# Deckelplatine_v091.net
KiCad netlist of a schematic drawn in EAGLE
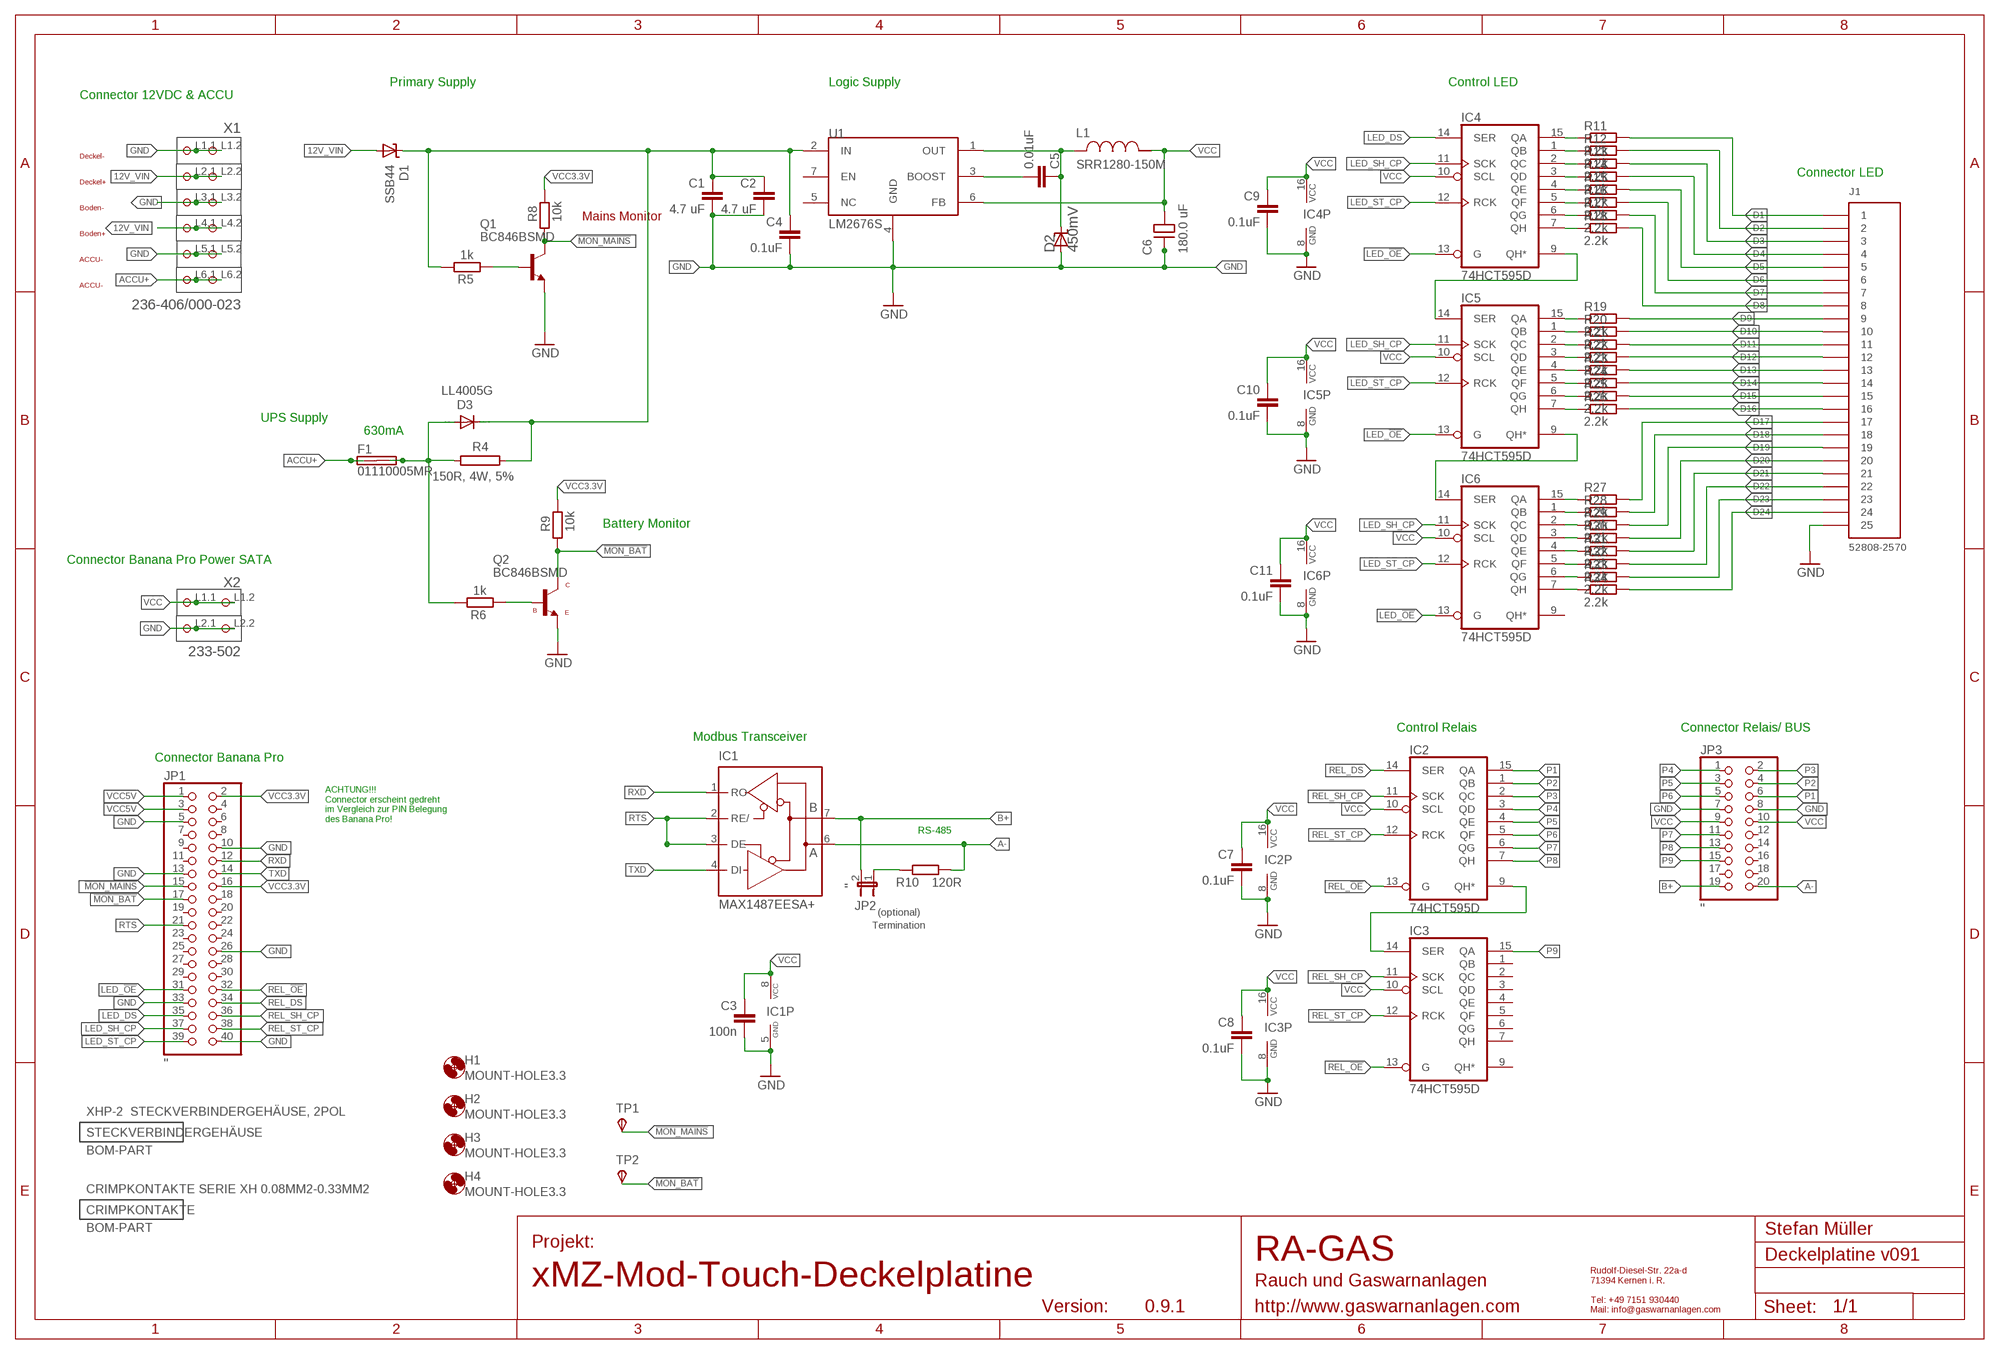
[diagram p0: schematic, sheet 1]

(export (version "E")
  (design (tool "Eeschema 10.0.6"))
  (components
    (comp (ref "C1")
      (value "4.7 uF")
      (footprint "eagle-import:GRM21BR61E475MA12L")
      (fields (field (name "MANUFACTURER_PART_NUMBER") "GRM21BR61E475MA12L") (field (name "MF") "MURATA"))
      (libsource (lib "eagle-import") (part "GRM21BR61E475MA12L"))
    )
    (comp (ref "C2")
      (value "4.7 uF")
      (footprint "eagle-import:GRM21BR61E475MA12L")
      (fields (field (name "MANUFACTURER_PART_NUMBER") "GRM21BR61E475MA12L") (field (name "MF") "MURATA"))
      (libsource (lib "eagle-import") (part "GRM21BR61E475MA12L"))
    )
    (comp (ref "C3")
      (value "100n")
      (footprint "eagle-import:C0603")
      (fields
        (field (name "MF") "KEMET")
        (field (name "MPN") "C0603C104K8RACTU")
        (field (name "PARTNO") "ECHU-16-100N")
      )
      (libsource (lib "eagle-import") (part "C-EUC0603"))
    )
    (comp (ref "C4")
      (value "0.1uF")
      (footprint "eagle-import:0805")
      (fields (field (name "MANUFACTURER_PART_NUMBER") "08053C104KAT2A") (field (name "MF") "AVX"))
      (libsource (lib "eagle-import") (part "08053C104KAT2A"))
    )
    (comp (ref "C5")
      (value "0.01uF")
      (footprint "eagle-import:GRM216R71H103KA01D")
      (fields (field (name "MANUFACTURER_PART_NUMBER") "GRM216R71H103KA01D") (field (name "MF") "MURATA"))
      (libsource (lib "eagle-import") (part "GRM216R71H103KA01D"))
    )
    (comp (ref "C6")
      (value "180.0 uF")
      (footprint "eagle-import:SM_RADIAL_10MM")
      (fields
        (field (name "MF") "PANASONIC ELECTRONIC COMPONENTS")
        (field (name "MPN") "16SVP180MX")
        (field (name "PARTNO") "RAD FC 560/35")
      )
      (libsource (lib "eagle-import") (part "16SVP180MSM_RADIAL_10MM"))
    )
    (comp (ref "C7")
      (value "0.1uF")
      (footprint "eagle-import:C0603")
      (fields
        (field (name "MF") "KEMET")
        (field (name "MPN") "C0603C104K8RACTU")
        (field (name "PARTNO") "SMD TAN.0,1/35")
      )
      (libsource (lib "eagle-import") (part "C-EUC0603"))
    )
    (comp (ref "C8")
      (value "0.1uF")
      (footprint "eagle-import:C0603")
      (fields
        (field (name "MF") "KEMET")
        (field (name "MPN") "C0603C104K8RACTU")
        (field (name "PARTNO") "SMD TAN.0,1/35")
      )
      (libsource (lib "eagle-import") (part "C-EUC0603"))
    )
    (comp (ref "C9")
      (value "0.1uF")
      (footprint "eagle-import:C0603")
      (fields
        (field (name "MF") "KEMET")
        (field (name "MPN") "C0603C104K8RACTU")
        (field (name "PARTNO") "SMD TAN.0,1/35")
      )
      (libsource (lib "eagle-import") (part "C-EUC0603"))
    )
    (comp (ref "C10")
      (value "0.1uF")
      (footprint "eagle-import:C0603")
      (fields
        (field (name "MF") "KEMET")
        (field (name "MPN") "C0603C104K8RACTU")
        (field (name "PARTNO") "SMD TAN.0,1/35")
      )
      (libsource (lib "eagle-import") (part "C-EUC0603"))
    )
    (comp (ref "C11")
      (value "0.1uF")
      (footprint "eagle-import:C0603")
      (fields
        (field (name "MF") "KEMET")
        (field (name "MPN") "C0603C104K8RACTU")
        (field (name "PARTNO") "SMD TAN.0,1/35")
      )
      (libsource (lib "eagle-import") (part "C-EUC0603"))
    )
    (comp (ref "D1")
      (value "SSB44")
      (footprint "eagle-import:SMBJ")
      (fields (field (name "MF") "VISHAY") (field (name "MPN") "SSB44-E3/52T"))
      (libsource (lib "eagle-import") (part "SUPPRESSOR-SMBJ"))
    )
    (comp (ref "D2")
      (value "450mV")
      (footprint "eagle-import:SMB")
      (fields (field (name "MANUFACTURER_PART_NUMBER") "B340LB-13-F") (field (name "MF") "DIODES INC."))
      (libsource (lib "eagle-import") (part "B340LB-13-F"))
    )
    (comp (ref "D3")
      (value "LL4005G")
      (footprint "eagle-import:MELF-MLL41")
      (fields (field (name "MF") "TAIWAN SEMICONDUCTOR"))
      (libsource (lib "eagle-import") (part "DIODE-MELF-MLL41"))
    )
    (comp (ref "F1")
      (value "01110005MR")
      (footprint "eagle-import:01110005MR")
      (fields (field (name "MF") "LITTELFUSE"))
      (libsource (lib "eagle-import") (part "01110005MR"))
    )
    (comp (ref "H1")
      (value "MOUNT-HOLE3.3")
      (footprint "eagle-import:3,3")
      (libsource (lib "eagle-import") (part "MOUNT-HOLE3.3"))
    )
    (comp (ref "H2")
      (value "MOUNT-HOLE3.3")
      (footprint "eagle-import:3,3")
      (libsource (lib "eagle-import") (part "MOUNT-HOLE3.3"))
    )
    (comp (ref "H3")
      (value "MOUNT-HOLE3.3")
      (footprint "eagle-import:3,3")
      (libsource (lib "eagle-import") (part "MOUNT-HOLE3.3"))
    )
    (comp (ref "H4")
      (value "MOUNT-HOLE3.3")
      (footprint "eagle-import:3,3")
      (libsource (lib "eagle-import") (part "MOUNT-HOLE3.3"))
    )
    (comp (ref "IC1")
      (value "MAX1487EESA+")
      (footprint "eagle-import:SO08")
      (fields
        (field (name "MF") "MAXIM")
        (field (name "MPN") "MAX481CSA")
        (field (name "MF_1") "MAXIM INTEGRATED PRODUCTS")
        (field (name "MPN_1") "MAX1487EESA+")
        (field (name "OC_FARNELL") "1593310")
        (field (name "PARTNO") "MAX481CSA")
      )
      (libsource (lib "eagle-import") (part "MAX481CSA"))
    )
    (comp (ref "IC2")
      (value "74HCT595D")
      (footprint "eagle-import:SO16")
      (fields
        (field (name "MF") "NXP")
        (field (name "MPN") "74HCT595D")
        (field (name "OC_FARNELL") "2098004")
        (field (name "PARTNO") "SMD HC 595")
      )
      (libsource (lib "eagle-import") (part "74595DHCT"))
    )
    (comp (ref "IC3")
      (value "74HCT595D")
      (footprint "eagle-import:SO16")
      (fields
        (field (name "MF") "NXP")
        (field (name "MPN") "74HCT595D")
        (field (name "OC_FARNELL") "2098004")
        (field (name "PARTNO") "SMD HC 595")
      )
      (libsource (lib "eagle-import") (part "74595DHCT"))
    )
    (comp (ref "IC4")
      (value "74HCT595D")
      (footprint "eagle-import:SO16")
      (fields
        (field (name "MF") "NXP")
        (field (name "MPN") "74HCT595D")
        (field (name "OC_FARNELL") "2098004")
        (field (name "PARTNO") "SMD HC 595")
      )
      (libsource (lib "eagle-import") (part "74595DHCT"))
    )
    (comp (ref "IC5")
      (value "74HCT595D")
      (footprint "eagle-import:SO16")
      (fields
        (field (name "MF") "NXP")
        (field (name "MPN") "74HCT595D")
        (field (name "OC_FARNELL") "2098004")
        (field (name "PARTNO") "SMD HC 595")
      )
      (libsource (lib "eagle-import") (part "74595DHCT"))
    )
    (comp (ref "IC6")
      (value "74HCT595D")
      (footprint "eagle-import:SO16")
      (fields
        (field (name "MF") "NXP")
        (field (name "MPN") "74HCT595D")
        (field (name "OC_FARNELL") "2098004")
        (field (name "PARTNO") "SMD HC 595")
      )
      (libsource (lib "eagle-import") (part "74595DHCT"))
    )
    (comp (ref "J1")
      (value "52808-2570")
      (footprint "eagle-import:52808-2570")
      (fields (field (name "MF") "MOLEX"))
      (libsource (lib "eagle-import") (part "52808-2570"))
    )
    (comp (ref "JP1")
      (value "''")
      (footprint "eagle-import:2X20")
      (fields (field (name "MF") "HARWIN") (field (name "MPN") "M20-6112045"))
      (libsource (lib "eagle-import") (part "PINHD-2X20"))
    )
    (comp (ref "JP2")
      (value "''")
      (footprint "eagle-import:JP1")
      (fields (field (name "MF") "TE CONNECTIVITY / AMP") (field (name "MPN") "825433-2"))
      (libsource (lib "eagle-import") (part "JP1E"))
    )
    (comp (ref "JP3")
      (value "''")
      (footprint "eagle-import:2X10")
      (fields (field (name "MF") "TE CONNECTIVITY / AMP") (field (name "MPN") "5103308-5"))
      (libsource (lib "eagle-import") (part "PINHD-2X10"))
    )
    (comp (ref "L1")
      (value "SRR1280-150M")
      (footprint "eagle-import:SRR1280")
      (fields (field (name "MF") "COILCRAFT") (field (name "MPN") "MSS1278-153MLD"))
      (libsource (lib "eagle-import") (part "SRR1280-150M"))
    )
    (comp (ref "Q1")
      (value "BC846BSMD")
      (footprint "eagle-import:SOT23")
      (fields (field (name "MF") "NXP") (field (name "MPN") "BC846,215"))
      (libsource (lib "eagle-import") (part "BC846SMDB"))
    )
    (comp (ref "Q2")
      (value "BC846BSMD")
      (footprint "eagle-import:SOT23")
      (fields (field (name "MF") "NXP") (field (name "MPN") "BC846,215"))
      (libsource (lib "eagle-import") (part "BC846SMDB"))
    )
    (comp (ref "R4")
      (value "150R, 4W, 5%")
      (footprint "eagle-import:KH206-8")
      (fields
        (field (name "MF") "TE CONNECTIVITY / CGS")
        (field (name "MPN") "ER74150RJT")
        (field (name "OC_FARNELL") "1751842")
      )
      (libsource (lib "eagle-import") (part "RKH206-8"))
    )
    (comp (ref "R5")
      (value "1k")
      (footprint "eagle-import:R1210")
      (fields (field (name "MF") "PANASONIC ELECTRONIC COMPONENTS") (field (name "MPN") "ERJP14F1001U"))
      (libsource (lib "eagle-import") (part "rcl_R-EU_R1210"))
    )
    (comp (ref "R6")
      (value "1k")
      (footprint "eagle-import:R1210")
      (fields (field (name "MF") "PANASONIC ELECTRONIC COMPONENTS") (field (name "MPN") "ERJP14F1001U"))
      (libsource (lib "eagle-import") (part "rcl_R-EU_R1210"))
    )
    (comp (ref "R8")
      (value "10k")
      (footprint "eagle-import:R1210")
      (fields (field (name "MF") "PANASONIC ELECTRONIC COMPONENTS") (field (name "MPN") "ERJP14F1002U"))
      (libsource (lib "eagle-import") (part "rcl_R-EU_R1210"))
    )
    (comp (ref "R9")
      (value "10k")
      (footprint "eagle-import:R1210")
      (fields (field (name "MF") "PANASONIC ELECTRONIC COMPONENTS") (field (name "MPN") "ERJP14F1002U"))
      (libsource (lib "eagle-import") (part "rcl_R-EU_R1210"))
    )
    (comp (ref "R10")
      (value "120R")
      (footprint "eagle-import:R1206")
      (fields (field (name "MF") "TE CONNECTIVITY") (field (name "MPN") "CRGH1206F120R"))
      (libsource (lib "eagle-import") (part "rcl_R-EU_R1206"))
    )
    (comp (ref "R11")
      (value "2.2k")
      (footprint "eagle-import:R0603")
      (fields
        (field (name "MF") "YAGEO (PHYCOMP)")
        (field (name "MPN") "RC0603FR-072K2L")
        (field (name "PARTNO") "SMD-0603 2,2K")
      )
      (libsource (lib "eagle-import") (part "R-EU_R0603"))
    )
    (comp (ref "R12")
      (value "2.2k")
      (footprint "eagle-import:R0603")
      (fields
        (field (name "MF") "YAGEO (PHYCOMP)")
        (field (name "MPN") "RC0603FR-072K2L")
        (field (name "PARTNO") "SMD-0603 2,2K")
      )
      (libsource (lib "eagle-import") (part "R-EU_R0603"))
    )
    (comp (ref "R13")
      (value "2.2k")
      (footprint "eagle-import:R0603")
      (fields
        (field (name "MF") "YAGEO (PHYCOMP)")
        (field (name "MPN") "RC0603FR-072K2L")
        (field (name "PARTNO") "SMD-0603 2,2K")
      )
      (libsource (lib "eagle-import") (part "R-EU_R0603"))
    )
    (comp (ref "R14")
      (value "2.2k")
      (footprint "eagle-import:R0603")
      (fields
        (field (name "MF") "YAGEO (PHYCOMP)")
        (field (name "MPN") "RC0603FR-072K2L")
        (field (name "PARTNO") "SMD-0603 2,2K")
      )
      (libsource (lib "eagle-import") (part "R-EU_R0603"))
    )
    (comp (ref "R15")
      (value "2.2k")
      (footprint "eagle-import:R0603")
      (fields
        (field (name "MF") "YAGEO (PHYCOMP)")
        (field (name "MPN") "RC0603FR-072K2L")
        (field (name "PARTNO") "SMD-0603 2,2K")
      )
      (libsource (lib "eagle-import") (part "R-EU_R0603"))
    )
    (comp (ref "R16")
      (value "2.2k")
      (footprint "eagle-import:R0603")
      (fields
        (field (name "MF") "YAGEO (PHYCOMP)")
        (field (name "MPN") "RC0603FR-072K2L")
        (field (name "PARTNO") "SMD-0603 2,2K")
      )
      (libsource (lib "eagle-import") (part "R-EU_R0603"))
    )
    (comp (ref "R17")
      (value "2.2k")
      (footprint "eagle-import:R0603")
      (fields
        (field (name "MF") "YAGEO (PHYCOMP)")
        (field (name "MPN") "RC0603FR-072K2L")
        (field (name "PARTNO") "SMD-0603 2,2K")
      )
      (libsource (lib "eagle-import") (part "R-EU_R0603"))
    )
    (comp (ref "R18")
      (value "2.2k")
      (footprint "eagle-import:R0603")
      (fields
        (field (name "MF") "YAGEO (PHYCOMP)")
        (field (name "MPN") "RC0603FR-072K2L")
        (field (name "PARTNO") "SMD-0603 2,2K")
      )
      (libsource (lib "eagle-import") (part "R-EU_R0603"))
    )
    (comp (ref "R19")
      (value "2.2k")
      (footprint "eagle-import:R0603")
      (fields
        (field (name "MF") "YAGEO (PHYCOMP)")
        (field (name "MPN") "RC0603FR-072K2L")
        (field (name "PARTNO") "SMD-0603 2,2K")
      )
      (libsource (lib "eagle-import") (part "R-EU_R0603"))
    )
    (comp (ref "R20")
      (value "2.2k")
      (footprint "eagle-import:R0603")
      (fields
        (field (name "MF") "YAGEO (PHYCOMP)")
        (field (name "MPN") "RC0603FR-072K2L")
        (field (name "PARTNO") "SMD-0603 2,2K")
      )
      (libsource (lib "eagle-import") (part "R-EU_R0603"))
    )
    (comp (ref "R21")
      (value "2.2k")
      (footprint "eagle-import:R0603")
      (fields
        (field (name "MF") "YAGEO (PHYCOMP)")
        (field (name "MPN") "RC0603FR-072K2L")
        (field (name "PARTNO") "SMD-0603 2,2K")
      )
      (libsource (lib "eagle-import") (part "R-EU_R0603"))
    )
    (comp (ref "R22")
      (value "2.2k")
      (footprint "eagle-import:R0603")
      (fields
        (field (name "MF") "YAGEO (PHYCOMP)")
        (field (name "MPN") "RC0603FR-072K2L")
        (field (name "PARTNO") "SMD-0603 2,2K")
      )
      (libsource (lib "eagle-import") (part "R-EU_R0603"))
    )
    (comp (ref "R23")
      (value "2.2k")
      (footprint "eagle-import:R0603")
      (fields
        (field (name "MF") "YAGEO (PHYCOMP)")
        (field (name "MPN") "RC0603FR-072K2L")
        (field (name "PARTNO") "SMD-0603 2,2K")
      )
      (libsource (lib "eagle-import") (part "R-EU_R0603"))
    )
    (comp (ref "R24")
      (value "2.2k")
      (footprint "eagle-import:R0603")
      (fields
        (field (name "MF") "YAGEO (PHYCOMP)")
        (field (name "MPN") "RC0603FR-072K2L")
        (field (name "PARTNO") "SMD-0603 2,2K")
      )
      (libsource (lib "eagle-import") (part "R-EU_R0603"))
    )
    (comp (ref "R25")
      (value "2.2k")
      (footprint "eagle-import:R0603")
      (fields
        (field (name "MF") "YAGEO (PHYCOMP)")
        (field (name "MPN") "RC0603FR-072K2L")
        (field (name "PARTNO") "SMD-0603 2,2K")
      )
      (libsource (lib "eagle-import") (part "R-EU_R0603"))
    )
    (comp (ref "R26")
      (value "2.2k")
      (footprint "eagle-import:R0603")
      (fields
        (field (name "MF") "YAGEO (PHYCOMP)")
        (field (name "MPN") "RC0603FR-072K2L")
        (field (name "PARTNO") "SMD-0603 2,2K")
      )
      (libsource (lib "eagle-import") (part "R-EU_R0603"))
    )
    (comp (ref "R27")
      (value "2.2k")
      (footprint "eagle-import:R0603")
      (fields
        (field (name "MF") "YAGEO (PHYCOMP)")
        (field (name "MPN") "RC0603FR-072K2L")
        (field (name "PARTNO") "SMD-0603 2,2K")
      )
      (libsource (lib "eagle-import") (part "R-EU_R0603"))
    )
    (comp (ref "R28")
      (value "2.2k")
      (footprint "eagle-import:R0603")
      (fields
        (field (name "MF") "YAGEO (PHYCOMP)")
        (field (name "MPN") "RC0603FR-072K2L")
        (field (name "PARTNO") "SMD-0603 2,2K")
      )
      (libsource (lib "eagle-import") (part "R-EU_R0603"))
    )
    (comp (ref "R29")
      (value "2.2k")
      (footprint "eagle-import:R0603")
      (fields
        (field (name "MF") "YAGEO (PHYCOMP)")
        (field (name "MPN") "RC0603FR-072K2L")
        (field (name "PARTNO") "SMD-0603 2,2K")
      )
      (libsource (lib "eagle-import") (part "R-EU_R0603"))
    )
    (comp (ref "R30")
      (value "2.2k")
      (footprint "eagle-import:R0603")
      (fields
        (field (name "MF") "YAGEO (PHYCOMP)")
        (field (name "MPN") "RC0603FR-072K2L")
        (field (name "PARTNO") "SMD-0603 2,2K")
      )
      (libsource (lib "eagle-import") (part "R-EU_R0603"))
    )
    (comp (ref "R31")
      (value "2.2k")
      (footprint "eagle-import:R0603")
      (fields
        (field (name "MF") "YAGEO (PHYCOMP)")
        (field (name "MPN") "RC0603FR-072K2L")
        (field (name "PARTNO") "SMD-0603 2,2K")
      )
      (libsource (lib "eagle-import") (part "R-EU_R0603"))
    )
    (comp (ref "R32")
      (value "2.2k")
      (footprint "eagle-import:R0603")
      (fields
        (field (name "MF") "YAGEO (PHYCOMP)")
        (field (name "MPN") "RC0603FR-072K2L")
        (field (name "PARTNO") "SMD-0603 2,2K")
      )
      (libsource (lib "eagle-import") (part "R-EU_R0603"))
    )
    (comp (ref "R33")
      (value "2.2k")
      (footprint "eagle-import:R0603")
      (fields
        (field (name "MF") "YAGEO (PHYCOMP)")
        (field (name "MPN") "RC0603FR-072K2L")
        (field (name "PARTNO") "SMD-0603 2,2K")
      )
      (libsource (lib "eagle-import") (part "R-EU_R0603"))
    )
    (comp (ref "R34")
      (value "2.2k")
      (footprint "eagle-import:R0603")
      (fields
        (field (name "MF") "YAGEO (PHYCOMP)")
        (field (name "MPN") "RC0603FR-072K2L")
        (field (name "PARTNO") "SMD-0603 2,2K")
      )
      (libsource (lib "eagle-import") (part "R-EU_R0603"))
    )
    (comp (ref "TP1")
      (value "TPSB1,27")
      (footprint "eagle-import:B1,27")
      (libsource (lib "eagle-import") (part "TPSB1,27"))
    )
    (comp (ref "TP2")
      (value "TPSB1,27")
      (footprint "eagle-import:B1,27")
      (libsource (lib "eagle-import") (part "TPSB1,27"))
    )
    (comp (ref "U1")
      (value "LM2676S")
      (footprint "eagle-import:TO-263-7")
      (fields (field (name "MF") "TEXAS INSTRUMENTS") (field (name "MPN") "LM2676S-5.0/NOPB"))
      (libsource (lib "eagle-import") (part "LM2676S"))
    )
    (comp (ref "X1")
      (value "236-406/000-023")
      (footprint "eagle-import:P-236-406")
      (fields (field (name "MF") "WAGO") (field (name "MPN") "236-406"))
      (libsource (lib "eagle-import") (part "236-406/000-023"))
    )
    (comp (ref "X2")
      (value "233-502")
      (footprint "eagle-import:P-233-502")
      (fields (field (name "MF") "WAGO") (field (name "MPN") "233-502."))
      (libsource (lib "eagle-import") (part "233-502"))
    )
  )
  (nets
    (net (code "1") (name "/LED_~{OE}") (class "Default")
      (node (ref "IC4") (pin "13") (pinfunction "G_13") (pintype "input"))
      (node (ref "IC5") (pin "13") (pinfunction "G_13") (pintype "input"))
      (node (ref "IC6") (pin "13") (pinfunction "G_13") (pintype "input"))
      (node (ref "JP1") (pin "31") (pinfunction "31_31") (pintype "passive"))
    )
    (net (code "2") (name "/REL_~{OE}") (class "Default")
      (node (ref "IC2") (pin "13") (pinfunction "G_13") (pintype "input"))
      (node (ref "IC3") (pin "13") (pinfunction "G_13") (pintype "input"))
      (node (ref "JP1") (pin "32") (pinfunction "32_32") (pintype "passive"))
    )
    (net (code "3") (name "/~{MON_BAT}") (class "Default")
      (node (ref "JP1") (pin "17") (pinfunction "17_17") (pintype "passive"))
      (node (ref "Q2") (pin "3") (pinfunction "C_3") (pintype "passive"))
      (node (ref "R9") (pin "1") (pinfunction "1_1") (pintype "passive"))
      (node (ref "TP2") (pin "TP") (pinfunction "PP_TP") (pintype "input"))
    )
    (net (code "4") (name "/~{MON_MAINS}") (class "Default")
      (node (ref "JP1") (pin "15") (pinfunction "15_15") (pintype "passive"))
      (node (ref "Q1") (pin "3") (pinfunction "C_3") (pintype "passive"))
      (node (ref "R8") (pin "1") (pinfunction "1_1") (pintype "passive"))
      (node (ref "TP1") (pin "TP") (pinfunction "PP_TP") (pintype "input"))
    )
    (net (code "5") (name "12V_VIN") (class "Default")
      (node (ref "C1") (pin "1") (pinfunction "1_1") (pintype "passive"))
      (node (ref "C2") (pin "1") (pinfunction "1_1") (pintype "passive"))
      (node (ref "C4") (pin "1") (pinfunction "1_1") (pintype "passive"))
      (node (ref "D1") (pin "A") (pinfunction "A_A") (pintype "passive"))
      (node (ref "D1") (pin "C") (pinfunction "C_C") (pintype "passive"))
      (node (ref "D3") (pin "C") (pinfunction "C_C") (pintype "passive"))
      (node (ref "R4") (pin "2") (pinfunction "2_2") (pintype "passive"))
      (node (ref "R5") (pin "2") (pinfunction "2_2") (pintype "passive"))
      (node (ref "U1") (pin "2") (pinfunction "IN_2") (pintype "power_in"))
      (node (ref "X1") (pin "L2.1") (pinfunction "P2.1_L2.1") (pintype "bidirectional"))
      (node (ref "X1") (pin "L2.2") (pinfunction "P2.2_L2.2") (pintype "bidirectional"))
      (node (ref "X1") (pin "L4.1") (pinfunction "P4.1_L4.1") (pintype "bidirectional"))
      (node (ref "X1") (pin "L4.2") (pinfunction "P4.2_L4.2") (pintype "bidirectional"))
    )
    (net (code "6") (name "A-") (class "Default")
      (node (ref "IC1") (pin "6") (pinfunction "A_6") (pintype "passive"))
      (node (ref "JP3") (pin "20") (pinfunction "20_20") (pintype "passive"))
      (node (ref "R10") (pin "2") (pinfunction "2_2") (pintype "passive"))
    )
    (net (code "7") (name "ACCU+") (class "Default")
      (node (ref "D3") (pin "A") (pinfunction "A_A") (pintype "passive"))
      (node (ref "F1") (pin "1A") (pinfunction "1A_1A") (pintype "passive"))
      (node (ref "F1") (pin "1B") (pinfunction "1B_1B") (pintype "passive"))
      (node (ref "F1") (pin "2A") (pinfunction "2A_2A") (pintype "passive"))
      (node (ref "F1") (pin "2B") (pinfunction "2B_2B") (pintype "passive"))
      (node (ref "R4") (pin "1") (pinfunction "1_1") (pintype "passive"))
      (node (ref "R6") (pin "2") (pinfunction "2_2") (pintype "passive"))
      (node (ref "X1") (pin "L6.1") (pinfunction "P6.1_L6.1") (pintype "bidirectional"))
      (node (ref "X1") (pin "L6.2") (pinfunction "P6.2_L6.2") (pintype "bidirectional"))
    )
    (net (code "8") (name "B+") (class "Default")
      (node (ref "IC1") (pin "7") (pinfunction "B_7") (pintype "passive"))
      (node (ref "JP2") (pin "2") (pinfunction "2_2") (pintype "passive"))
      (node (ref "JP3") (pin "19") (pinfunction "19_19") (pintype "passive"))
    )
    (net (code "9") (name "D1") (class "Default")
      (node (ref "J1") (pin "1") (pinfunction "1_1") (pintype "bidirectional"))
      (node (ref "R11") (pin "2") (pinfunction "2_2") (pintype "passive"))
    )
    (net (code "10") (name "D2") (class "Default")
      (node (ref "J1") (pin "2") (pinfunction "2_2") (pintype "bidirectional"))
      (node (ref "R12") (pin "2") (pinfunction "2_2") (pintype "passive"))
    )
    (net (code "11") (name "D3") (class "Default")
      (node (ref "J1") (pin "3") (pinfunction "3_3") (pintype "bidirectional"))
      (node (ref "R13") (pin "2") (pinfunction "2_2") (pintype "passive"))
    )
    (net (code "12") (name "D4") (class "Default")
      (node (ref "J1") (pin "4") (pinfunction "4_4") (pintype "bidirectional"))
      (node (ref "R14") (pin "2") (pinfunction "2_2") (pintype "passive"))
    )
    (net (code "13") (name "D5") (class "Default")
      (node (ref "J1") (pin "5") (pinfunction "5_5") (pintype "bidirectional"))
      (node (ref "R15") (pin "2") (pinfunction "2_2") (pintype "passive"))
    )
    (net (code "14") (name "D6") (class "Default")
      (node (ref "J1") (pin "6") (pinfunction "6_6") (pintype "bidirectional"))
      (node (ref "R16") (pin "2") (pinfunction "2_2") (pintype "passive"))
    )
    (net (code "15") (name "D7") (class "Default")
      (node (ref "J1") (pin "7") (pinfunction "7_7") (pintype "bidirectional"))
      (node (ref "R17") (pin "2") (pinfunction "2_2") (pintype "passive"))
    )
    (net (code "16") (name "D8") (class "Default")
      (node (ref "J1") (pin "8") (pinfunction "8_8") (pintype "bidirectional"))
      (node (ref "R18") (pin "2") (pinfunction "2_2") (pintype "passive"))
    )
    (net (code "17") (name "D9") (class "Default")
      (node (ref "J1") (pin "9") (pinfunction "9_9") (pintype "bidirectional"))
      (node (ref "R19") (pin "2") (pinfunction "2_2") (pintype "passive"))
    )
    (net (code "18") (name "D10") (class "Default")
      (node (ref "J1") (pin "10") (pinfunction "10_10") (pintype "bidirectional"))
      (node (ref "R20") (pin "2") (pinfunction "2_2") (pintype "passive"))
    )
    (net (code "19") (name "D11") (class "Default")
      (node (ref "J1") (pin "11") (pinfunction "11_11") (pintype "bidirectional"))
      (node (ref "R21") (pin "2") (pinfunction "2_2") (pintype "passive"))
    )
    (net (code "20") (name "D12") (class "Default")
      (node (ref "J1") (pin "12") (pinfunction "12_12") (pintype "bidirectional"))
      (node (ref "R22") (pin "2") (pinfunction "2_2") (pintype "passive"))
    )
    (net (code "21") (name "D13") (class "Default")
      (node (ref "J1") (pin "13") (pinfunction "13_13") (pintype "bidirectional"))
      (node (ref "R23") (pin "2") (pinfunction "2_2") (pintype "passive"))
    )
    (net (code "22") (name "D14") (class "Default")
      (node (ref "J1") (pin "14") (pinfunction "14_14") (pintype "bidirectional"))
      (node (ref "R24") (pin "2") (pinfunction "2_2") (pintype "passive"))
    )
    (net (code "23") (name "D15") (class "Default")
      (node (ref "J1") (pin "15") (pinfunction "15_15") (pintype "bidirectional"))
      (node (ref "R25") (pin "2") (pinfunction "2_2") (pintype "passive"))
    )
    (net (code "24") (name "D16") (class "Default")
      (node (ref "J1") (pin "16") (pinfunction "16_16") (pintype "bidirectional"))
      (node (ref "R26") (pin "2") (pinfunction "2_2") (pintype "passive"))
    )
    (net (code "25") (name "D17") (class "Default")
      (node (ref "J1") (pin "17") (pinfunction "17_17") (pintype "bidirectional"))
      (node (ref "R27") (pin "2") (pinfunction "2_2") (pintype "passive"))
    )
    (net (code "26") (name "D18") (class "Default")
      (node (ref "J1") (pin "18") (pinfunction "18_18") (pintype "bidirectional"))
      (node (ref "R28") (pin "2") (pinfunction "2_2") (pintype "passive"))
    )
    (net (code "27") (name "D19") (class "Default")
      (node (ref "J1") (pin "19") (pinfunction "19_19") (pintype "bidirectional"))
      (node (ref "R29") (pin "2") (pinfunction "2_2") (pintype "passive"))
    )
    (net (code "28") (name "D20") (class "Default")
      (node (ref "J1") (pin "20") (pinfunction "20_20") (pintype "bidirectional"))
      (node (ref "R30") (pin "2") (pinfunction "2_2") (pintype "passive"))
    )
    (net (code "29") (name "D21") (class "Default")
      (node (ref "J1") (pin "21") (pinfunction "21_21") (pintype "bidirectional"))
      (node (ref "R31") (pin "2") (pinfunction "2_2") (pintype "passive"))
    )
    (net (code "30") (name "D22") (class "Default")
      (node (ref "J1") (pin "22") (pinfunction "22_22") (pintype "bidirectional"))
      (node (ref "R32") (pin "2") (pinfunction "2_2") (pintype "passive"))
    )
    (net (code "31") (name "D23") (class "Default")
      (node (ref "J1") (pin "23") (pinfunction "23_23") (pintype "bidirectional"))
      (node (ref "R33") (pin "2") (pinfunction "2_2") (pintype "passive"))
    )
    (net (code "32") (name "D24") (class "Default")
      (node (ref "J1") (pin "24") (pinfunction "24_24") (pintype "bidirectional"))
      (node (ref "R34") (pin "2") (pinfunction "2_2") (pintype "passive"))
    )
    (net (code "33") (name "GND") (class "Default")
      (node (ref "C1") (pin "2") (pinfunction "2_2") (pintype "passive"))
      (node (ref "C10") (pin "2") (pinfunction "2_2") (pintype "passive"))
      (node (ref "C11") (pin "2") (pinfunction "2_2") (pintype "passive"))
      (node (ref "C2") (pin "2") (pinfunction "2_2") (pintype "passive"))
      (node (ref "C3") (pin "2") (pinfunction "2_2") (pintype "passive"))
      (node (ref "C4") (pin "2") (pinfunction "2_2") (pintype "passive"))
      (node (ref "C6") (pin "2") (pinfunction "-_2") (pintype "passive"))
      (node (ref "C7") (pin "2") (pinfunction "2_2") (pintype "passive"))
      (node (ref "C8") (pin "2") (pinfunction "2_2") (pintype "passive"))
      (node (ref "C9") (pin "2") (pinfunction "2_2") (pintype "passive"))
      (node (ref "D2") (pin "A") (pinfunction "A_A") (pintype "passive"))
      (node (ref "IC1") (pin "5") (pinfunction "GND_5") (pintype "power_in"))
      (node (ref "IC2") (pin "8") (pinfunction "GND_8") (pintype "power_in"))
      (node (ref "IC3") (pin "8") (pinfunction "GND_8") (pintype "power_in"))
      (node (ref "IC4") (pin "8") (pinfunction "GND_8") (pintype "power_in"))
      (node (ref "IC5") (pin "8") (pinfunction "GND_8") (pintype "power_in"))
      (node (ref "IC6") (pin "8") (pinfunction "GND_8") (pintype "power_in"))
      (node (ref "J1") (pin "25") (pinfunction "25_25") (pintype "bidirectional"))
      (node (ref "JP1") (pin "10") (pinfunction "10_10") (pintype "passive"))
      (node (ref "JP1") (pin "13") (pinfunction "13_13") (pintype "passive"))
      (node (ref "JP1") (pin "26") (pinfunction "26_26") (pintype "passive"))
      (node (ref "JP1") (pin "33") (pinfunction "33_33") (pintype "passive"))
      (node (ref "JP1") (pin "40") (pinfunction "40_40") (pintype "passive"))
      (node (ref "JP1") (pin "5") (pinfunction "5_5") (pintype "passive"))
      (node (ref "JP3") (pin "7") (pinfunction "7_7") (pintype "passive"))
      (node (ref "JP3") (pin "8") (pinfunction "8_8") (pintype "passive"))
      (node (ref "Q1") (pin "2") (pinfunction "E_2") (pintype "passive"))
      (node (ref "Q2") (pin "2") (pinfunction "E_2") (pintype "passive"))
      (node (ref "U1") (pin "4") (pinfunction "GND_4") (pintype "power_in"))
      (node (ref "X1") (pin "L1.1") (pinfunction "P1.1_L1.1") (pintype "bidirectional"))
      (node (ref "X1") (pin "L1.2") (pinfunction "P1.2_L1.2") (pintype "bidirectional"))
      (node (ref "X1") (pin "L3.1") (pinfunction "P3.1_L3.1") (pintype "bidirectional"))
      (node (ref "X1") (pin "L3.2") (pinfunction "P3.2_L3.2") (pintype "bidirectional"))
      (node (ref "X1") (pin "L5.1") (pinfunction "P5.1_L5.1") (pintype "bidirectional"))
      (node (ref "X1") (pin "L5.2") (pinfunction "P5.2_L5.2") (pintype "bidirectional"))
      (node (ref "X2") (pin "L2.1") (pinfunction "P2.1_L2.1") (pintype "bidirectional"))
      (node (ref "X2") (pin "L2.2") (pinfunction "P2.2_L2.2") (pintype "bidirectional"))
    )
    (net (code "34") (name "LED_DS") (class "Default")
      (node (ref "IC4") (pin "14") (pinfunction "SER_14") (pintype "input"))
      (node (ref "JP1") (pin "35") (pinfunction "35_35") (pintype "passive"))
    )
    (net (code "35") (name "LED_SH_CP") (class "Default")
      (node (ref "IC4") (pin "11") (pinfunction "SCK_11") (pintype "input"))
      (node (ref "IC5") (pin "11") (pinfunction "SCK_11") (pintype "input"))
      (node (ref "IC6") (pin "11") (pinfunction "SCK_11") (pintype "input"))
      (node (ref "JP1") (pin "37") (pinfunction "37_37") (pintype "passive"))
    )
    (net (code "36") (name "LED_ST_CP") (class "Default")
      (node (ref "IC4") (pin "12") (pinfunction "RCK_12") (pintype "input"))
      (node (ref "IC5") (pin "12") (pinfunction "RCK_12") (pintype "input"))
      (node (ref "IC6") (pin "12") (pinfunction "RCK_12") (pintype "input"))
      (node (ref "JP1") (pin "39") (pinfunction "39_39") (pintype "passive"))
    )
    (net (code "37") (name "Net-(IC2A-QH*)") (class "Default")
      (node (ref "IC2") (pin "9") (pinfunction "QH*_9") (pintype "tri_state"))
      (node (ref "IC3") (pin "14") (pinfunction "SER_14") (pintype "input"))
    )
    (net (code "38") (name "Net-(IC4A-QA)") (class "Default")
      (node (ref "IC4") (pin "15") (pinfunction "QA_15") (pintype "tri_state"))
      (node (ref "R11") (pin "1") (pinfunction "1_1") (pintype "passive"))
    )
    (net (code "39") (name "Net-(IC4A-QB)") (class "Default")
      (node (ref "IC4") (pin "1") (pinfunction "QB_1") (pintype "tri_state"))
      (node (ref "R12") (pin "1") (pinfunction "1_1") (pintype "passive"))
    )
    (net (code "40") (name "Net-(IC4A-QC)") (class "Default")
      (node (ref "IC4") (pin "2") (pinfunction "QC_2") (pintype "tri_state"))
      (node (ref "R13") (pin "1") (pinfunction "1_1") (pintype "passive"))
    )
    (net (code "41") (name "Net-(IC4A-QD)") (class "Default")
      (node (ref "IC4") (pin "3") (pinfunction "QD_3") (pintype "tri_state"))
      (node (ref "R14") (pin "1") (pinfunction "1_1") (pintype "passive"))
    )
    (net (code "42") (name "Net-(IC4A-QE)") (class "Default")
      (node (ref "IC4") (pin "4") (pinfunction "QE_4") (pintype "tri_state"))
      (node (ref "R15") (pin "1") (pinfunction "1_1") (pintype "passive"))
    )
    (net (code "43") (name "Net-(IC4A-QF)") (class "Default")
      (node (ref "IC4") (pin "5") (pinfunction "QF_5") (pintype "tri_state"))
      (node (ref "R16") (pin "1") (pinfunction "1_1") (pintype "passive"))
    )
    (net (code "44") (name "Net-(IC4A-QG)") (class "Default")
      (node (ref "IC4") (pin "6") (pinfunction "QG_6") (pintype "tri_state"))
      (node (ref "R17") (pin "1") (pinfunction "1_1") (pintype "passive"))
    )
    (net (code "45") (name "Net-(IC4A-QH)") (class "Default")
      (node (ref "IC4") (pin "7") (pinfunction "QH_7") (pintype "tri_state"))
      (node (ref "R18") (pin "1") (pinfunction "1_1") (pintype "passive"))
    )
    (net (code "46") (name "Net-(IC4A-QH*)") (class "Default")
      (node (ref "IC4") (pin "9") (pinfunction "QH*_9") (pintype "tri_state"))
      (node (ref "IC5") (pin "14") (pinfunction "SER_14") (pintype "input"))
    )
    (net (code "47") (name "Net-(IC5A-QA)") (class "Default")
      (node (ref "IC5") (pin "15") (pinfunction "QA_15") (pintype "tri_state"))
      (node (ref "R19") (pin "1") (pinfunction "1_1") (pintype "passive"))
    )
    (net (code "48") (name "Net-(IC5A-QB)") (class "Default")
      (node (ref "IC5") (pin "1") (pinfunction "QB_1") (pintype "tri_state"))
      (node (ref "R20") (pin "1") (pinfunction "1_1") (pintype "passive"))
    )
    (net (code "49") (name "Net-(IC5A-QC)") (class "Default")
      (node (ref "IC5") (pin "2") (pinfunction "QC_2") (pintype "tri_state"))
      (node (ref "R21") (pin "1") (pinfunction "1_1") (pintype "passive"))
    )
    (net (code "50") (name "Net-(IC5A-QD)") (class "Default")
      (node (ref "IC5") (pin "3") (pinfunction "QD_3") (pintype "tri_state"))
      (node (ref "R22") (pin "1") (pinfunction "1_1") (pintype "passive"))
    )
    (net (code "51") (name "Net-(IC5A-QE)") (class "Default")
      (node (ref "IC5") (pin "4") (pinfunction "QE_4") (pintype "tri_state"))
      (node (ref "R23") (pin "1") (pinfunction "1_1") (pintype "passive"))
    )
    (net (code "52") (name "Net-(IC5A-QF)") (class "Default")
      (node (ref "IC5") (pin "5") (pinfunction "QF_5") (pintype "tri_state"))
      (node (ref "R24") (pin "1") (pinfunction "1_1") (pintype "passive"))
    )
    (net (code "53") (name "Net-(IC5A-QG)") (class "Default")
      (node (ref "IC5") (pin "6") (pinfunction "QG_6") (pintype "tri_state"))
      (node (ref "R25") (pin "1") (pinfunction "1_1") (pintype "passive"))
    )
    (net (code "54") (name "Net-(IC5A-QH)") (class "Default")
      (node (ref "IC5") (pin "7") (pinfunction "QH_7") (pintype "tri_state"))
      (node (ref "R26") (pin "1") (pinfunction "1_1") (pintype "passive"))
    )
    (net (code "55") (name "Net-(IC5A-QH*)") (class "Default")
      (node (ref "IC5") (pin "9") (pinfunction "QH*_9") (pintype "tri_state"))
      (node (ref "IC6") (pin "14") (pinfunction "SER_14") (pintype "input"))
    )
    (net (code "56") (name "Net-(IC6A-QA)") (class "Default")
      (node (ref "IC6") (pin "15") (pinfunction "QA_15") (pintype "tri_state"))
      (node (ref "R27") (pin "1") (pinfunction "1_1") (pintype "passive"))
    )
    (net (code "57") (name "Net-(IC6A-QB)") (class "Default")
      (node (ref "IC6") (pin "1") (pinfunction "QB_1") (pintype "tri_state"))
      (node (ref "R28") (pin "1") (pinfunction "1_1") (pintype "passive"))
    )
    (net (code "58") (name "Net-(IC6A-QC)") (class "Default")
      (node (ref "IC6") (pin "2") (pinfunction "QC_2") (pintype "tri_state"))
      (node (ref "R29") (pin "1") (pinfunction "1_1") (pintype "passive"))
    )
    (net (code "59") (name "Net-(IC6A-QD)") (class "Default")
      (node (ref "IC6") (pin "3") (pinfunction "QD_3") (pintype "tri_state"))
      (node (ref "R30") (pin "1") (pinfunction "1_1") (pintype "passive"))
    )
    (net (code "60") (name "Net-(IC6A-QE)") (class "Default")
      (node (ref "IC6") (pin "4") (pinfunction "QE_4") (pintype "tri_state"))
      (node (ref "R31") (pin "1") (pinfunction "1_1") (pintype "passive"))
    )
    (net (code "61") (name "Net-(IC6A-QF)") (class "Default")
      (node (ref "IC6") (pin "5") (pinfunction "QF_5") (pintype "tri_state"))
      (node (ref "R32") (pin "1") (pinfunction "1_1") (pintype "passive"))
    )
    (net (code "62") (name "Net-(IC6A-QG)") (class "Default")
      (node (ref "IC6") (pin "6") (pinfunction "QG_6") (pintype "tri_state"))
      (node (ref "R33") (pin "1") (pinfunction "1_1") (pintype "passive"))
    )
    (net (code "63") (name "Net-(IC6A-QH)") (class "Default")
      (node (ref "IC6") (pin "7") (pinfunction "QH_7") (pintype "tri_state"))
      (node (ref "R34") (pin "1") (pinfunction "1_1") (pintype "passive"))
    )
    (net (code "64") (name "Net-(JP2-Pad1)") (class "Default")
      (node (ref "JP2") (pin "1") (pinfunction "1_1") (pintype "passive"))
      (node (ref "R10") (pin "1") (pinfunction "1_1") (pintype "passive"))
    )
    (net (code "65") (name "Net-(Q1-B)") (class "Default")
      (node (ref "Q1") (pin "1") (pinfunction "B_1") (pintype "passive"))
      (node (ref "R5") (pin "1") (pinfunction "1_1") (pintype "passive"))
    )
    (net (code "66") (name "Net-(Q2-B)") (class "Default")
      (node (ref "Q2") (pin "1") (pinfunction "B_1") (pintype "passive"))
      (node (ref "R6") (pin "1") (pinfunction "1_1") (pintype "passive"))
    )
    (net (code "67") (name "Net-(U1-BOOST)") (class "Default")
      (node (ref "C5") (pin "2") (pinfunction "2_2") (pintype "passive"))
      (node (ref "U1") (pin "3") (pinfunction "BOOST_3") (pintype "bidirectional"))
    )
    (net (code "68") (name "Net-(U1-OUT)") (class "Default")
      (node (ref "C5") (pin "1") (pinfunction "1_1") (pintype "passive"))
      (node (ref "D2") (pin "C") (pinfunction "C_C") (pintype "passive"))
      (node (ref "L1") (pin "1") (pinfunction "1_1") (pintype "passive"))
      (node (ref "U1") (pin "1") (pinfunction "OUT_1") (pintype "bidirectional"))
    )
    (net (code "69") (name "P1") (class "Default")
      (node (ref "IC2") (pin "15") (pinfunction "QA_15") (pintype "tri_state"))
      (node (ref "JP3") (pin "6") (pinfunction "6_6") (pintype "passive"))
    )
    (net (code "70") (name "P2") (class "Default")
      (node (ref "IC2") (pin "1") (pinfunction "QB_1") (pintype "tri_state"))
      (node (ref "JP3") (pin "4") (pinfunction "4_4") (pintype "passive"))
    )
    (net (code "71") (name "P3") (class "Default")
      (node (ref "IC2") (pin "2") (pinfunction "QC_2") (pintype "tri_state"))
      (node (ref "JP3") (pin "2") (pinfunction "2_2") (pintype "passive"))
    )
    (net (code "72") (name "P4") (class "Default")
      (node (ref "IC2") (pin "3") (pinfunction "QD_3") (pintype "tri_state"))
      (node (ref "JP3") (pin "1") (pinfunction "1_1") (pintype "passive"))
    )
    (net (code "73") (name "P5") (class "Default")
      (node (ref "IC2") (pin "4") (pinfunction "QE_4") (pintype "tri_state"))
      (node (ref "JP3") (pin "3") (pinfunction "3_3") (pintype "passive"))
    )
    (net (code "74") (name "P6") (class "Default")
      (node (ref "IC2") (pin "5") (pinfunction "QF_5") (pintype "tri_state"))
      (node (ref "JP3") (pin "5") (pinfunction "5_5") (pintype "passive"))
    )
    (net (code "75") (name "P7") (class "Default")
      (node (ref "IC2") (pin "6") (pinfunction "QG_6") (pintype "tri_state"))
      (node (ref "JP3") (pin "11") (pinfunction "11_11") (pintype "passive"))
    )
    (net (code "76") (name "P8") (class "Default")
      (node (ref "IC2") (pin "7") (pinfunction "QH_7") (pintype "tri_state"))
      (node (ref "JP3") (pin "13") (pinfunction "13_13") (pintype "passive"))
    )
    (net (code "77") (name "P9") (class "Default")
      (node (ref "IC3") (pin "15") (pinfunction "QA_15") (pintype "tri_state"))
      (node (ref "JP3") (pin "15") (pinfunction "15_15") (pintype "passive"))
    )
    (net (code "78") (name "REL_DS") (class "Default")
      (node (ref "IC2") (pin "14") (pinfunction "SER_14") (pintype "input"))
      (node (ref "JP1") (pin "34") (pinfunction "34_34") (pintype "passive"))
    )
    (net (code "79") (name "REL_SH_CP") (class "Default")
      (node (ref "IC2") (pin "11") (pinfunction "SCK_11") (pintype "input"))
      (node (ref "IC3") (pin "11") (pinfunction "SCK_11") (pintype "input"))
      (node (ref "JP1") (pin "36") (pinfunction "36_36") (pintype "passive"))
    )
    (net (code "80") (name "REL_ST_CP") (class "Default")
      (node (ref "IC2") (pin "12") (pinfunction "RCK_12") (pintype "input"))
      (node (ref "IC3") (pin "12") (pinfunction "RCK_12") (pintype "input"))
      (node (ref "JP1") (pin "38") (pinfunction "38_38") (pintype "passive"))
    )
    (net (code "81") (name "RTS") (class "Default")
      (node (ref "IC1") (pin "2") (pinfunction "RE/_2") (pintype "input"))
      (node (ref "IC1") (pin "3") (pinfunction "DE_3") (pintype "input"))
      (node (ref "JP1") (pin "21") (pinfunction "21_21") (pintype "passive"))
    )
    (net (code "82") (name "RXD") (class "Default")
      (node (ref "IC1") (pin "1") (pinfunction "RO_1") (pintype "output"))
      (node (ref "JP1") (pin "12") (pinfunction "12_12") (pintype "passive"))
    )
    (net (code "83") (name "TXD") (class "Default")
      (node (ref "IC1") (pin "4") (pinfunction "DI_4") (pintype "input"))
      (node (ref "JP1") (pin "14") (pinfunction "14_14") (pintype "passive"))
    )
    (net (code "84") (name "VCC") (class "Default")
      (node (ref "C10") (pin "1") (pinfunction "1_1") (pintype "passive"))
      (node (ref "C11") (pin "1") (pinfunction "1_1") (pintype "passive"))
      (node (ref "C3") (pin "1") (pinfunction "1_1") (pintype "passive"))
      (node (ref "C6") (pin "1") (pinfunction "+_1") (pintype "passive"))
      (node (ref "C7") (pin "1") (pinfunction "1_1") (pintype "passive"))
      (node (ref "C8") (pin "1") (pinfunction "1_1") (pintype "passive"))
      (node (ref "C9") (pin "1") (pinfunction "1_1") (pintype "passive"))
      (node (ref "IC1") (pin "8") (pinfunction "VCC_8") (pintype "power_in"))
      (node (ref "IC2") (pin "10") (pinfunction "SCL_10") (pintype "input"))
      (node (ref "IC2") (pin "16") (pinfunction "VCC_16") (pintype "power_in"))
      (node (ref "IC3") (pin "10") (pinfunction "SCL_10") (pintype "input"))
      (node (ref "IC3") (pin "16") (pinfunction "VCC_16") (pintype "power_in"))
      (node (ref "IC4") (pin "10") (pinfunction "SCL_10") (pintype "input"))
      (node (ref "IC4") (pin "16") (pinfunction "VCC_16") (pintype "power_in"))
      (node (ref "IC5") (pin "10") (pinfunction "SCL_10") (pintype "input"))
      (node (ref "IC5") (pin "16") (pinfunction "VCC_16") (pintype "power_in"))
      (node (ref "IC6") (pin "10") (pinfunction "SCL_10") (pintype "input"))
      (node (ref "IC6") (pin "16") (pinfunction "VCC_16") (pintype "power_in"))
      (node (ref "JP3") (pin "10") (pinfunction "10_10") (pintype "passive"))
      (node (ref "JP3") (pin "9") (pinfunction "9_9") (pintype "passive"))
      (node (ref "L1") (pin "2") (pinfunction "2_2") (pintype "passive"))
      (node (ref "U1") (pin "6") (pinfunction "FB_6") (pintype "bidirectional"))
      (node (ref "X2") (pin "L1.1") (pinfunction "P1.1_L1.1") (pintype "bidirectional"))
      (node (ref "X2") (pin "L1.2") (pinfunction "P1.2_L1.2") (pintype "bidirectional"))
    )
    (net (code "85") (name "VCC3.3V") (class "Default")
      (node (ref "JP1") (pin "16") (pinfunction "16_16") (pintype "passive"))
      (node (ref "JP1") (pin "2") (pinfunction "2_2") (pintype "passive"))
      (node (ref "R8") (pin "2") (pinfunction "2_2") (pintype "passive"))
      (node (ref "R9") (pin "2") (pinfunction "2_2") (pintype "passive"))
    )
    (net (code "86") (name "VCC5V") (class "Default")
      (node (ref "JP1") (pin "1") (pinfunction "1_1") (pintype "passive"))
      (node (ref "JP1") (pin "3") (pinfunction "3_3") (pintype "passive"))
    )
    (net (code "87") (name "unconnected-(IC3A-QB-Pad1)") (class "Default")
      (node (ref "IC3") (pin "1") (pinfunction "QB_1") (pintype "tri_state"))
    )
    (net (code "88") (name "unconnected-(IC3A-QC-Pad2)") (class "Default")
      (node (ref "IC3") (pin "2") (pinfunction "QC_2") (pintype "tri_state"))
    )
    (net (code "89") (name "unconnected-(IC3A-QD-Pad3)") (class "Default")
      (node (ref "IC3") (pin "3") (pinfunction "QD_3") (pintype "tri_state"))
    )
    (net (code "90") (name "unconnected-(IC3A-QE-Pad4)") (class "Default")
      (node (ref "IC3") (pin "4") (pinfunction "QE_4") (pintype "tri_state"))
    )
    (net (code "91") (name "unconnected-(IC3A-QF-Pad5)") (class "Default")
      (node (ref "IC3") (pin "5") (pinfunction "QF_5") (pintype "tri_state"))
    )
    (net (code "92") (name "unconnected-(IC3A-QG-Pad6)") (class "Default")
      (node (ref "IC3") (pin "6") (pinfunction "QG_6") (pintype "tri_state"))
    )
    (net (code "93") (name "unconnected-(IC3A-QH*-Pad9)") (class "Default")
      (node (ref "IC3") (pin "9") (pinfunction "QH*_9") (pintype "tri_state"))
    )
    (net (code "94") (name "unconnected-(IC3A-QH-Pad7)") (class "Default")
      (node (ref "IC3") (pin "7") (pinfunction "QH_7") (pintype "tri_state"))
    )
    (net (code "95") (name "unconnected-(IC6A-QH*-Pad9)") (class "Default")
      (node (ref "IC6") (pin "9") (pinfunction "QH*_9") (pintype "tri_state"))
    )
    (net (code "96") (name "unconnected-(JP1-Pad4)") (class "Default")
      (node (ref "JP1") (pin "4") (pinfunction "4_4") (pintype "passive"))
    )
    (net (code "97") (name "unconnected-(JP1-Pad6)") (class "Default")
      (node (ref "JP1") (pin "6") (pinfunction "6_6") (pintype "passive"))
    )
    (net (code "98") (name "unconnected-(JP1-Pad7)") (class "Default")
      (node (ref "JP1") (pin "7") (pinfunction "7_7") (pintype "passive"))
    )
    (net (code "99") (name "unconnected-(JP1-Pad8)") (class "Default")
      (node (ref "JP1") (pin "8") (pinfunction "8_8") (pintype "passive"))
    )
    (net (code "100") (name "unconnected-(JP1-Pad9)") (class "Default")
      (node (ref "JP1") (pin "9") (pinfunction "9_9") (pintype "passive"))
    )
    (net (code "101") (name "unconnected-(JP1-Pad11)") (class "Default")
      (node (ref "JP1") (pin "11") (pinfunction "11_11") (pintype "passive"))
    )
    (net (code "102") (name "unconnected-(JP1-Pad18)") (class "Default")
      (node (ref "JP1") (pin "18") (pinfunction "18_18") (pintype "passive"))
    )
    (net (code "103") (name "unconnected-(JP1-Pad19)") (class "Default")
      (node (ref "JP1") (pin "19") (pinfunction "19_19") (pintype "passive"))
    )
    (net (code "104") (name "unconnected-(JP1-Pad20)") (class "Default")
      (node (ref "JP1") (pin "20") (pinfunction "20_20") (pintype "passive"))
    )
    (net (code "105") (name "unconnected-(JP1-Pad22)") (class "Default")
      (node (ref "JP1") (pin "22") (pinfunction "22_22") (pintype "passive"))
    )
    (net (code "106") (name "unconnected-(JP1-Pad23)") (class "Default")
      (node (ref "JP1") (pin "23") (pinfunction "23_23") (pintype "passive"))
    )
    (net (code "107") (name "unconnected-(JP1-Pad24)") (class "Default")
      (node (ref "JP1") (pin "24") (pinfunction "24_24") (pintype "passive"))
    )
    (net (code "108") (name "unconnected-(JP1-Pad25)") (class "Default")
      (node (ref "JP1") (pin "25") (pinfunction "25_25") (pintype "passive"))
    )
    (net (code "109") (name "unconnected-(JP1-Pad27)") (class "Default")
      (node (ref "JP1") (pin "27") (pinfunction "27_27") (pintype "passive"))
    )
    (net (code "110") (name "unconnected-(JP1-Pad28)") (class "Default")
      (node (ref "JP1") (pin "28") (pinfunction "28_28") (pintype "passive"))
    )
    (net (code "111") (name "unconnected-(JP1-Pad29)") (class "Default")
      (node (ref "JP1") (pin "29") (pinfunction "29_29") (pintype "passive"))
    )
    (net (code "112") (name "unconnected-(JP1-Pad30)") (class "Default")
      (node (ref "JP1") (pin "30") (pinfunction "30_30") (pintype "passive"))
    )
    (net (code "113") (name "unconnected-(JP3-Pad12)") (class "Default")
      (node (ref "JP3") (pin "12") (pinfunction "12_12") (pintype "passive"))
    )
    (net (code "114") (name "unconnected-(JP3-Pad14)") (class "Default")
      (node (ref "JP3") (pin "14") (pinfunction "14_14") (pintype "passive"))
    )
    (net (code "115") (name "unconnected-(JP3-Pad16)") (class "Default")
      (node (ref "JP3") (pin "16") (pinfunction "16_16") (pintype "passive"))
    )
    (net (code "116") (name "unconnected-(JP3-Pad17)") (class "Default")
      (node (ref "JP3") (pin "17") (pinfunction "17_17") (pintype "passive"))
    )
    (net (code "117") (name "unconnected-(JP3-Pad18)") (class "Default")
      (node (ref "JP3") (pin "18") (pinfunction "18_18") (pintype "passive"))
    )
    (net (code "118") (name "unconnected-(U1-EN-Pad7)") (class "Default")
      (node (ref "U1") (pin "7") (pinfunction "EN_7") (pintype "bidirectional"))
    )
    (net (code "119") (name "unconnected-(U1-NC-Pad5)") (class "Default")
      (node (ref "U1") (pin "5") (pinfunction "NC_5") (pintype "no_connect"))
    )
  )
)
